# untitled.net
KiCad netlist of a schematic drawn in EAGLE
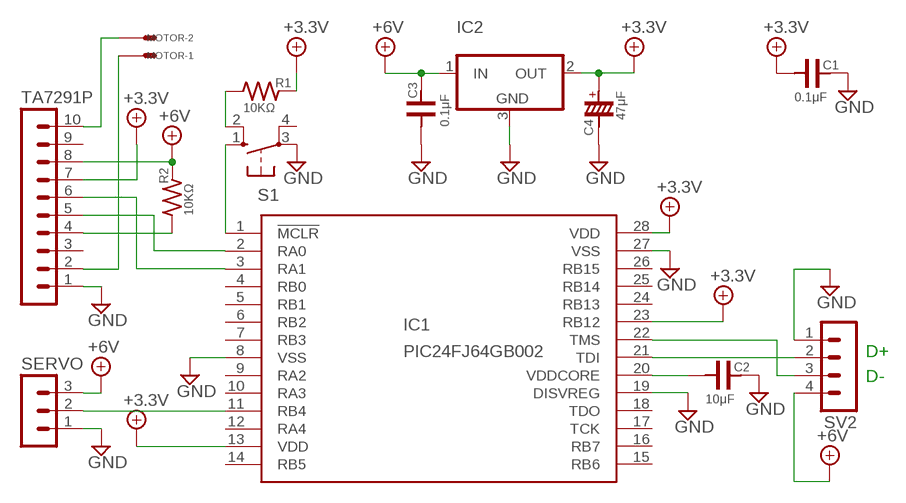
[diagram p0: schematic, sheet 1]

(export (version "E")
  (design (tool "Eeschema 10.0.6"))
  (components
    (comp (ref "C1")
      (value "0.1μF")
      (footprint "eagle-import:C25-25X44")
      (libsource (lib "eagle-import") (part "C25"))
    )
    (comp (ref "C2")
      (value "10μF")
      (footprint "eagle-import:C25-25X44")
      (libsource (lib "eagle-import") (part "C25"))
    )
    (comp (ref "C3")
      (value "0.1μF")
      (footprint "eagle-import:C25-25X44")
      (libsource (lib "eagle-import") (part "C25"))
    )
    (comp (ref "C4")
      (value "47μF")
      (footprint "eagle-import:TT2D5L")
      (libsource (lib "eagle-import") (part "POLCL"))
    )
    (comp (ref "IC1")
      (value "PIC24FJ64GB002")
      (footprint "eagle-import:DIL28-3")
      (fields (field (name "MPN") "PIC24FJ64GA002-I/SP"))
      (libsource (lib "eagle-import") (part "PIC24FJ64GB002"))
    )
    (comp (ref "IC2")
      (value "TA48MV")
      (footprint "eagle-import:HSIP3-P2.30B_V")
      (libsource (lib "eagle-import") (part "TA48MV"))
    )
    (comp (ref "MOTOR")
      (value "CON2S")
      (footprint "eagle-import:CON2")
      (libsource (lib "eagle-import") (part "CON2S"))
    )
    (comp (ref "R1")
      (value "10KΩ")
      (footprint "eagle-import:0204_5")
      (libsource (lib "eagle-import") (part "R"))
    )
    (comp (ref "R2")
      (value "10KΩ")
      (footprint "eagle-import:0204_5")
      (libsource (lib "eagle-import") (part "R"))
    )
    (comp (ref "S1")
      (value "10-XX")
      (footprint "eagle-import:B3F-10XX")
      (fields (field (name "MPN") "B3F-1000"))
      (libsource (lib "eagle-import") (part "10-XX"))
    )
    (comp (ref "SERVO")
      (value "MA03-1")
      (footprint "eagle-import:MA03-1")
      (libsource (lib "eagle-import") (part "MA03-1"))
    )
    (comp (ref "SV2")
      (value "MA04-1")
      (footprint "eagle-import:MA04-1")
      (libsource (lib "eagle-import") (part "MA04-1"))
    )
    (comp (ref "TA7291P")
      (value "MA10-1")
      (footprint "eagle-import:MA10-1")
      (libsource (lib "eagle-import") (part "MA10-1"))
    )
  )
  (nets
    (net (code "1") (name "+3.3V") (class "Default")
      (node (ref "C1") (pin "P$1") (pinfunction "1_P$1") (pintype "passive"))
      (node (ref "C4") (pin "P$1") (pinfunction "P$1_P$1") (pintype "passive"))
      (node (ref "IC1") (pin "13") (pinfunction "VDD_13") (pintype "power_in"))
      (node (ref "IC1") (pin "23") (pinfunction "RB12_23") (pintype "bidirectional"))
      (node (ref "IC1") (pin "28") (pinfunction "VDD_28") (pintype "power_in"))
      (node (ref "IC2") (pin "2") (pinfunction "OUT_2") (pintype "passive"))
      (node (ref "R1") (pin "2") (pinfunction "2_2") (pintype "passive"))
      (node (ref "TA7291P") (pin "7") (pinfunction "7_7") (pintype "passive"))
    )
    (net (code "2") (name "+6V") (class "Default")
      (node (ref "C3") (pin "P$2") (pinfunction "2_P$2") (pintype "passive"))
      (node (ref "IC2") (pin "1") (pinfunction "IN_1") (pintype "input"))
      (node (ref "R2") (pin "2") (pinfunction "2_2") (pintype "passive"))
      (node (ref "SERVO") (pin "3") (pinfunction "3_3") (pintype "passive"))
      (node (ref "SV2") (pin "4") (pinfunction "4_4") (pintype "passive"))
      (node (ref "TA7291P") (pin "8") (pinfunction "8_8") (pintype "passive"))
    )
    (net (code "3") (name "GND") (class "Default")
      (node (ref "C1") (pin "P$2") (pinfunction "2_P$2") (pintype "passive"))
      (node (ref "C2") (pin "P$2") (pinfunction "2_P$2") (pintype "passive"))
      (node (ref "C3") (pin "P$1") (pinfunction "1_P$1") (pintype "passive"))
      (node (ref "C4") (pin "P$2") (pinfunction "P$2_P$2") (pintype "passive"))
      (node (ref "IC1") (pin "19") (pinfunction "DISVREG_19") (pintype "passive"))
      (node (ref "IC1") (pin "27") (pinfunction "VSS_27") (pintype "power_in"))
      (node (ref "IC1") (pin "8") (pinfunction "VSS_8") (pintype "power_in"))
      (node (ref "IC2") (pin "3") (pinfunction "GND_3") (pintype "passive"))
      (node (ref "S1") (pin "3") (pinfunction "P_3") (pintype "passive"))
      (node (ref "SERVO") (pin "1") (pinfunction "1_1") (pintype "passive"))
      (node (ref "SV2") (pin "1") (pinfunction "1_1") (pintype "passive"))
      (node (ref "TA7291P") (pin "1") (pinfunction "1_1") (pintype "passive"))
    )
    (net (code "4") (name "Net-(C2-1)") (class "Default")
      (node (ref "C2") (pin "P$1") (pinfunction "1_P$1") (pintype "passive"))
      (node (ref "IC1") (pin "20") (pinfunction "VDDCORE_20") (pintype "power_in"))
    )
    (net (code "5") (name "Net-(IC1-RA0)") (class "Default")
      (node (ref "IC1") (pin "2") (pinfunction "RA0_2") (pintype "bidirectional"))
      (node (ref "TA7291P") (pin "5") (pinfunction "5_5") (pintype "passive"))
    )
    (net (code "6") (name "Net-(IC1-RA1)") (class "Default")
      (node (ref "IC1") (pin "3") (pinfunction "RA1_3") (pintype "bidirectional"))
      (node (ref "TA7291P") (pin "6") (pinfunction "6_6") (pintype "passive"))
    )
    (net (code "7") (name "Net-(IC1-RB4)") (class "Default")
      (node (ref "IC1") (pin "11") (pinfunction "RB4_11") (pintype "bidirectional"))
      (node (ref "SERVO") (pin "2") (pinfunction "2_2") (pintype "passive"))
    )
    (net (code "8") (name "Net-(IC1-TDI)") (class "Default")
      (node (ref "IC1") (pin "21") (pinfunction "TDI_21") (pintype "input"))
      (node (ref "SV2") (pin "2") (pinfunction "2_2") (pintype "passive"))
    )
    (net (code "9") (name "Net-(IC1-TMS)") (class "Default")
      (node (ref "IC1") (pin "22") (pinfunction "TMS_22") (pintype "input"))
      (node (ref "SV2") (pin "3") (pinfunction "3_3") (pintype "passive"))
    )
    (net (code "10") (name "Net-(IC1-~{MCLR})") (class "Default")
      (node (ref "IC1") (pin "1") (pinfunction "~{MCLR}_1") (pintype "bidirectional"))
      (node (ref "S1") (pin "1") (pinfunction "S_1") (pintype "passive"))
    )
    (net (code "11") (name "Net-(MOTOR-PadP$1)") (class "Default")
      (node (ref "MOTOR") (pin "P$1") (pinfunction "P$1_P$1") (pintype "passive"))
      (node (ref "TA7291P") (pin "2") (pinfunction "2_2") (pintype "passive"))
    )
    (net (code "12") (name "Net-(MOTORB-P$1)") (class "Default")
      (node (ref "MOTOR") (pin "P$2") (pinfunction "P$1_P$2") (pintype "passive"))
      (node (ref "TA7291P") (pin "10") (pinfunction "10_10") (pintype "passive"))
    )
    (net (code "13") (name "Net-(R2-Pad1)") (class "Default")
      (node (ref "R2") (pin "1") (pinfunction "1_1") (pintype "passive"))
      (node (ref "TA7291P") (pin "4") (pinfunction "4_4") (pintype "passive"))
    )
    (net (code "14") (name "Net-(S1-S1)") (class "Default")
      (node (ref "R1") (pin "1") (pinfunction "1_1") (pintype "passive"))
      (node (ref "S1") (pin "2") (pinfunction "S1_2") (pintype "passive"))
    )
    (net (code "15") (name "unconnected-(IC1-RA2-Pad9)") (class "Default")
      (node (ref "IC1") (pin "9") (pinfunction "RA2_9") (pintype "bidirectional"))
    )
    (net (code "16") (name "unconnected-(IC1-RA3-Pad10)") (class "Default")
      (node (ref "IC1") (pin "10") (pinfunction "RA3_10") (pintype "bidirectional"))
    )
    (net (code "17") (name "unconnected-(IC1-RA4-Pad12)") (class "Default")
      (node (ref "IC1") (pin "12") (pinfunction "RA4_12") (pintype "bidirectional"))
    )
    (net (code "18") (name "unconnected-(IC1-RB0-Pad4)") (class "Default")
      (node (ref "IC1") (pin "4") (pinfunction "RB0_4") (pintype "bidirectional"))
    )
    (net (code "19") (name "unconnected-(IC1-RB1-Pad5)") (class "Default")
      (node (ref "IC1") (pin "5") (pinfunction "RB1_5") (pintype "bidirectional"))
    )
    (net (code "20") (name "unconnected-(IC1-RB2-Pad6)") (class "Default")
      (node (ref "IC1") (pin "6") (pinfunction "RB2_6") (pintype "bidirectional"))
    )
    (net (code "21") (name "unconnected-(IC1-RB3-Pad7)") (class "Default")
      (node (ref "IC1") (pin "7") (pinfunction "RB3_7") (pintype "bidirectional"))
    )
    (net (code "22") (name "unconnected-(IC1-RB5-Pad14)") (class "Default")
      (node (ref "IC1") (pin "14") (pinfunction "RB5_14") (pintype "bidirectional"))
    )
    (net (code "23") (name "unconnected-(IC1-RB6-Pad15)") (class "Default")
      (node (ref "IC1") (pin "15") (pinfunction "RB6_15") (pintype "bidirectional"))
    )
    (net (code "24") (name "unconnected-(IC1-RB7-Pad16)") (class "Default")
      (node (ref "IC1") (pin "16") (pinfunction "RB7_16") (pintype "bidirectional"))
    )
    (net (code "25") (name "unconnected-(IC1-RB13-Pad24)") (class "Default")
      (node (ref "IC1") (pin "24") (pinfunction "RB13_24") (pintype "bidirectional"))
    )
    (net (code "26") (name "unconnected-(IC1-RB14-Pad25)") (class "Default")
      (node (ref "IC1") (pin "25") (pinfunction "RB14_25") (pintype "bidirectional"))
    )
    (net (code "27") (name "unconnected-(IC1-RB15-Pad26)") (class "Default")
      (node (ref "IC1") (pin "26") (pinfunction "RB15_26") (pintype "bidirectional"))
    )
    (net (code "28") (name "unconnected-(IC1-TCK-Pad17)") (class "Default")
      (node (ref "IC1") (pin "17") (pinfunction "TCK_17") (pintype "input"))
    )
    (net (code "29") (name "unconnected-(IC1-TDO-Pad18)") (class "Default")
      (node (ref "IC1") (pin "18") (pinfunction "TDO_18") (pintype "output"))
    )
    (net (code "30") (name "unconnected-(S1-P1-Pad4)") (class "Default")
      (node (ref "S1") (pin "4") (pinfunction "P1_4") (pintype "passive"))
    )
    (net (code "31") (name "unconnected-(TA7291P-Pad3)") (class "Default")
      (node (ref "TA7291P") (pin "3") (pinfunction "3_3") (pintype "passive"))
    )
    (net (code "32") (name "unconnected-(TA7291P-Pad9)") (class "Default")
      (node (ref "TA7291P") (pin "9") (pinfunction "9_9") (pintype "passive"))
    )
  )
)
